# Sheet3.net
KiCad netlist of a schematic drawn in Altium Designer
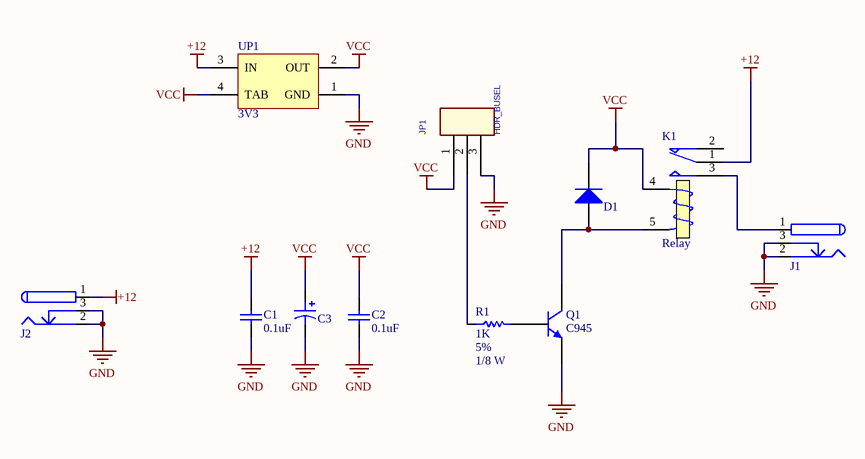
[diagram p0: Sheet3.SchDoc]

(export (version "E")
  (design (tool "Eeschema 10.0.6"))
  (components
    (comp (ref "C1")
      (value "0.1uF")
      (footprint "CAPC4817X12N")
      (description "CAP 1206")
      (fields (field (name "DESIGNER") "Abbas Basereh"))
      (libsource (lib "2017AbbasBasereh9365731239 -ver1") (part "CAP SMD 1206"))
    )
    (comp (ref "C2")
      (value "0.1uF")
      (footprint "CAPC4817X12N")
      (description "CAP 1206")
      (fields (field (name "DESIGNER") "Abbas Basereh"))
      (libsource (lib "2017AbbasBasereh9365731239 -ver1") (part "CAP SMD 1206"))
    )
    (comp (ref "C3")
      (value "100uF50V")
      (footprint "Cap electrolitic radial 6x7-2.5")
      (description "Cap electrolitic radial")
      (fields (field (name "DESIGNER") "Abbas Basereh"))
      (libsource (lib "2017AbbasBasereh9365731239 -ver1") (part "Cap ELECTROLITIC TOTAL SIZE"))
    )
    (comp (ref "D1")
      (value "1n4007")
      (footprint "DIOM4629X24N")
      (description "Standard Rectifiers")
      (fields (field (name "MANUFACTURER") "DC COMPONENTS") (field (name "DESIGNER") "Abbas Basereh"))
      (libsource (lib "2017AbbasBasereh9365731239 -ver1") (part "1n4007 SMD M7"))
    )
    (comp (ref "J1")
      (value "DC Power Jack")
      (footprint "DC Power Jack 1")
      (description "DC Power Jack. Center Pin 2.5mm. Diameter: 5.7mm")
      (fields (field (name "DESIGNER") "Ali Hafizi"))
      (libsource (lib "") (part "DC Power Jack_1"))
    )
    (comp (ref "J2")
      (value "DC Power Jack")
      (footprint "DC Power Jack 1")
      (description "DC Power Jack. Center Pin 2.5mm. Diameter: 5.7mm")
      (fields (field (name "DESIGNER") "Ali Hafizi"))
      (libsource (lib "4_5965406465417019807") (part "DC Power Jack"))
    )
    (comp (ref "JP1")
      (value "HDR_BUSEL")
      (footprint "HDR_1x3")
      (description "header or jumper box")
      (libsource (lib "2017AbbasBasereh9365731239 -ver1") (part "Header 1x3"))
    )
    (comp (ref "K1")
      (value "Relay")
      (footprint "Relay 15.40x12.10x13.10")
      (description "SPDT Relay")
      (fields (field (name "DESIGNER") "Eng. Saeid Jorablo"))
      (libsource (lib "My Library (1)") (part "Relay"))
    )
    (comp (ref "Q1")
      (value "C945")
      (footprint "SOT23_N")
      (description "NPN Silicon Epitaxial Planar Transistor")
      (fields (field (name "PUBLISHER") "Abbas Basereh"))
      (libsource (lib "2017AbbasBasereh9365731239 -ver1") (part "C945"))
    )
    (comp (ref "R1")
      (value "1K")
      (footprint "Res-(1/4)")
      (description "Resistor")
      (fields (field (name "TOLERANCE") "5%") (field (name "POWER") "1/8 W"))
      (libsource (lib "My Library") (part "Resistor"))
    )
    (comp (ref "UP1")
      (value "3V3")
      (footprint "SOT223_N")
      (description "x.x Volt, 800mA Low-Dropout Linear Regulator, 4-pin SOT-223")
      (fields (field (name "DESIGNER") "Ali Hafizi"))
      (libsource (lib "4_5965406465417019807") (part "AMS1117-x.x"))
    )
  )
  (nets
    (net (code "1") (name "+12") (class "Default")
      (node (ref "C1") (pin "2") (pinfunction "2_2") (pintype "passive"))
      (node (ref "J2") (pin "1") (pinfunction "1_1") (pintype "power_in"))
      (node (ref "K1") (pin "1") (pinfunction "COM_1") (pintype "passive"))
      (node (ref "UP1") (pin "3") (pinfunction "IN_3") (pintype "power_in"))
    )
    (net (code "2") (name "GND") (class "Default")
      (node (ref "C1") (pin "1") (pinfunction "1_1") (pintype "passive"))
      (node (ref "C2") (pin "1") (pinfunction "1_1") (pintype "passive"))
      (node (ref "C3") (pin "2") (pinfunction "2_2") (pintype "passive"))
      (node (ref "J1") (pin "2") (pinfunction "2_2") (pintype "power_in"))
      (node (ref "J1") (pin "3") (pinfunction "3_3") (pintype "power_in"))
      (node (ref "J2") (pin "2") (pinfunction "2_2") (pintype "power_in"))
      (node (ref "J2") (pin "3") (pinfunction "3_3") (pintype "power_in"))
      (node (ref "JP1") (pin "3") (pinfunction "3_3") (pintype "passive"))
      (node (ref "Q1") (pin "2") (pinfunction "E_2") (pintype "passive"))
      (node (ref "UP1") (pin "1") (pinfunction "GND_1") (pintype "power_in"))
    )
    (net (code "3") (name "Net-(D1-A)") (class "Default")
      (node (ref "D1") (pin "1") (pinfunction "A_1") (pintype "passive"))
      (node (ref "K1") (pin "5") (pinfunction "T2_5") (pintype "passive"))
      (node (ref "Q1") (pin "3") (pinfunction "C_3") (pintype "passive"))
    )
    (net (code "4") (name "Net-(JP1-Pad2)") (class "Default")
      (node (ref "JP1") (pin "2") (pinfunction "2_2") (pintype "passive"))
      (node (ref "R1") (pin "1") (pinfunction "1_1") (pintype "passive"))
    )
    (net (code "5") (name "Net-(K1-NO)") (class "Default")
      (node (ref "J1") (pin "1") (pinfunction "1_1") (pintype "power_in"))
      (node (ref "K1") (pin "3") (pinfunction "NO_3") (pintype "passive"))
    )
    (net (code "6") (name "Net-(Q1-B)") (class "Default")
      (node (ref "Q1") (pin "1") (pinfunction "B_1") (pintype "passive"))
      (node (ref "R1") (pin "2") (pinfunction "2_2") (pintype "passive"))
    )
    (net (code "7") (name "VCC") (class "Default")
      (node (ref "C2") (pin "2") (pinfunction "2_2") (pintype "passive"))
      (node (ref "C3") (pin "1") (pinfunction "1_1") (pintype "passive"))
      (node (ref "D1") (pin "2") (pinfunction "K_2") (pintype "passive"))
      (node (ref "JP1") (pin "1") (pinfunction "1_1") (pintype "passive"))
      (node (ref "K1") (pin "4") (pinfunction "T1_4") (pintype "passive"))
      (node (ref "UP1") (pin "2") (pinfunction "OUT_2") (pintype "power_in"))
      (node (ref "UP1") (pin "4") (pinfunction "TAB_4") (pintype "power_in"))
    )
    (net (code "8") (name "unconnected-(K1-NC-Pad2)") (class "Default")
      (node (ref "K1") (pin "2") (pinfunction "NC_2") (pintype "passive"))
    )
  )
)
